# OnOfre_EasyPlug_dev.net
KiCad netlist of a schematic drawn in EAGLE
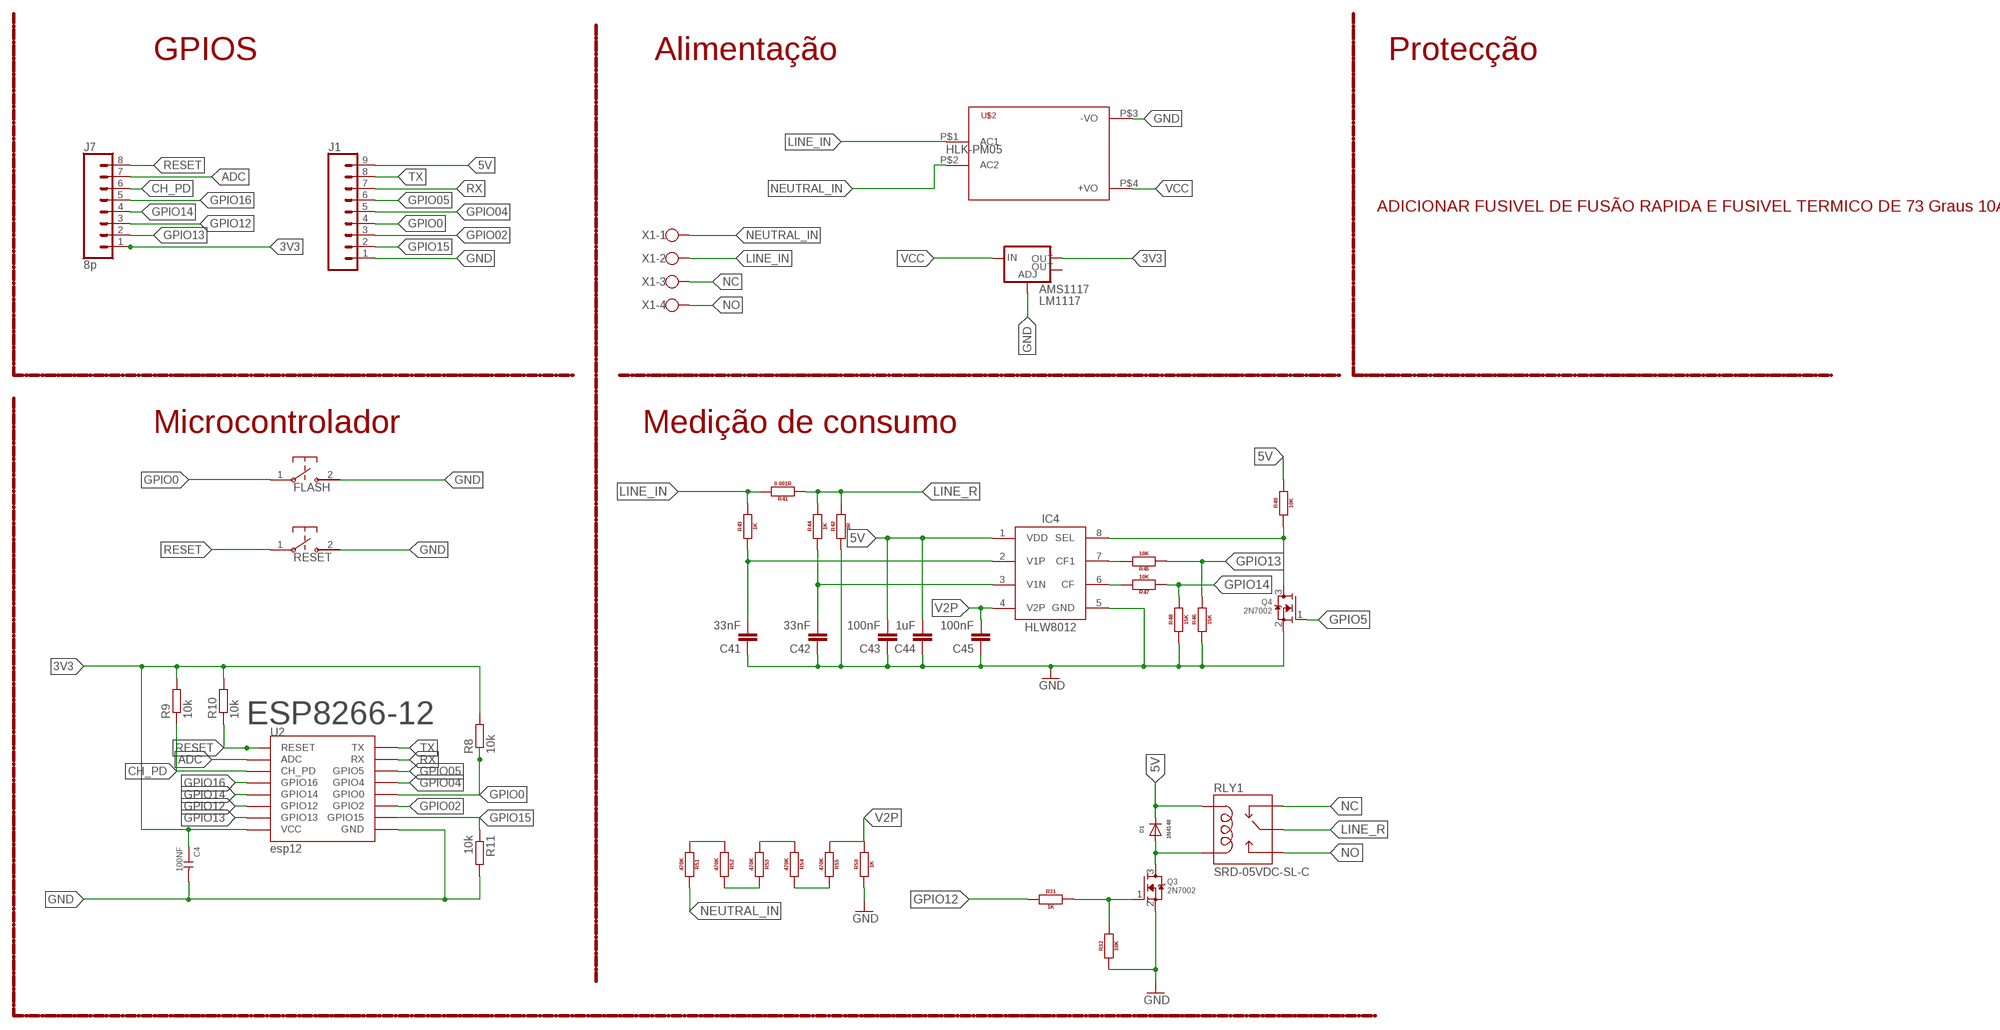
[diagram p0: schematic, sheet 1]

(export (version "E")
  (design (tool "Eeschema 10.0.6"))
  (components
    (comp (ref "AMS1117")
      (value "LM1117")
      (footprint "eagle-import:SOT223")
      (libsource (lib "eagle-import") (part "V_REG_LM1117SOT223"))
    )
    (comp (ref "C4")
      (value "100NF")
      (footprint "eagle-import:C1206")
      (fields (field (name "MPN") "CC1206KKX7RCBB102"))
      (libsource (lib "eagle-import") (part "CERAMIC-1NF-1KV-10%-X7R?(1206)"))
    )
    (comp (ref "C41")
      (value "33nF")
      (footprint "eagle-import:0805")
      (libsource (lib "eagle-import") (part "C-EU0805"))
    )
    (comp (ref "C42")
      (value "33nF")
      (footprint "eagle-import:0805")
      (libsource (lib "eagle-import") (part "C-EU0805"))
    )
    (comp (ref "C43")
      (value "100nF")
      (footprint "eagle-import:0805")
      (libsource (lib "eagle-import") (part "C-EU0805"))
    )
    (comp (ref "C44")
      (value "1uF")
      (footprint "eagle-import:0805")
      (libsource (lib "eagle-import") (part "C-EU0805"))
    )
    (comp (ref "C45")
      (value "100nF")
      (footprint "eagle-import:0805")
      (libsource (lib "eagle-import") (part "C-EU0805"))
    )
    (comp (ref "D1")
      (value "1N4148")
      (footprint "eagle-import:SOD80")
      (libsource (lib "eagle-import") (part "DIODE"))
    )
    (comp (ref "FLASH")
      (value "B3U-1000P-2P-SMD")
      (footprint "eagle-import:B3U-1000P")
      (fields (field (name "MANUFACTURER") "Omron") (field (name "MPN") "B3U-1000P"))
      (libsource (lib "eagle-import") (part "B3U-1000P"))
    )
    (comp (ref "IC4")
      (value "HLW8012")
      (footprint "eagle-import:SOP8")
      (libsource (lib "eagle-import") (part "HLW8012"))
    )
    (comp (ref "J1")
      (value "CONN_09")
      (footprint "eagle-import:1X09")
      (libsource (lib "eagle-import") (part "CONN_09"))
    )
    (comp (ref "J7")
      (value "8p")
      (footprint "eagle-import:1X08")
      (libsource (lib "eagle-import") (part "CONN_08{dblquote}"))
    )
    (comp (ref "Q3")
      (value "2N7002")
      (footprint "eagle-import:SOT23")
      (libsource (lib "eagle-import") (part "MOSFET-NREFLOW"))
    )
    (comp (ref "Q4")
      (value "2N7002")
      (footprint "eagle-import:SOT23")
      (libsource (lib "eagle-import") (part "MOSFET-NREFLOW"))
    )
    (comp (ref "R8")
      (value "10k")
      (footprint "eagle-import:R0603")
      (libsource (lib "eagle-import") (part "R-EU_R0603"))
    )
    (comp (ref "R9")
      (value "10k")
      (footprint "eagle-import:R0603")
      (libsource (lib "eagle-import") (part "R-EU_R0603"))
    )
    (comp (ref "R10")
      (value "10k")
      (footprint "eagle-import:R0603")
      (libsource (lib "eagle-import") (part "R-EU_R0603"))
    )
    (comp (ref "R11")
      (value "10k")
      (footprint "eagle-import:R0603")
      (libsource (lib "eagle-import") (part "R-EU_R0603"))
    )
    (comp (ref "R31")
      (value "1K")
      (footprint "eagle-import:0805")
      (libsource (lib "eagle-import") (part "RESISTOR0805"))
    )
    (comp (ref "R32")
      (value "10K")
      (footprint "eagle-import:0805")
      (libsource (lib "eagle-import") (part "RESISTOR0805"))
    )
    (comp (ref "R41")
      (value "0.001R")
      (footprint "eagle-import:2512")
      (libsource (lib "eagle-import") (part "RESISTOR2512"))
    )
    (comp (ref "R42")
      (value "0R")
      (footprint "eagle-import:1206")
      (libsource (lib "eagle-import") (part "RESISTOR1206"))
    )
    (comp (ref "R43")
      (value "1K")
      (footprint "eagle-import:0805")
      (libsource (lib "eagle-import") (part "RESISTOR0805"))
    )
    (comp (ref "R44")
      (value "1K")
      (footprint "eagle-import:0805")
      (libsource (lib "eagle-import") (part "RESISTOR0805"))
    )
    (comp (ref "R45")
      (value "10K")
      (footprint "eagle-import:0805")
      (libsource (lib "eagle-import") (part "RESISTOR0805"))
    )
    (comp (ref "R46")
      (value "15K")
      (footprint "eagle-import:0805")
      (libsource (lib "eagle-import") (part "RESISTOR0805"))
    )
    (comp (ref "R47")
      (value "10K")
      (footprint "eagle-import:0805")
      (libsource (lib "eagle-import") (part "RESISTOR0805"))
    )
    (comp (ref "R48")
      (value "15K")
      (footprint "eagle-import:0805")
      (libsource (lib "eagle-import") (part "RESISTOR0805"))
    )
    (comp (ref "R49")
      (value "10K")
      (footprint "eagle-import:0805")
      (libsource (lib "eagle-import") (part "RESISTOR0805"))
    )
    (comp (ref "R50")
      (value "1K")
      (footprint "eagle-import:0805")
      (libsource (lib "eagle-import") (part "RESISTOR0805"))
    )
    (comp (ref "R51")
      (value "470K")
      (footprint "eagle-import:0805")
      (libsource (lib "eagle-import") (part "RESISTOR0805"))
    )
    (comp (ref "R52")
      (value "470K")
      (footprint "eagle-import:0805")
      (libsource (lib "eagle-import") (part "RESISTOR0805"))
    )
    (comp (ref "R53")
      (value "470K")
      (footprint "eagle-import:0805")
      (libsource (lib "eagle-import") (part "RESISTOR0805"))
    )
    (comp (ref "R54")
      (value "470K")
      (footprint "eagle-import:0805")
      (libsource (lib "eagle-import") (part "RESISTOR0805"))
    )
    (comp (ref "R55")
      (value "470K")
      (footprint "eagle-import:0805")
      (libsource (lib "eagle-import") (part "RESISTOR0805"))
    )
    (comp (ref "RESET")
      (value "B3U-1000P-2P-SMD")
      (footprint "eagle-import:B3U-1000P")
      (fields (field (name "MANUFACTURER") "Omron") (field (name "MPN") "B3U-1000P"))
      (libsource (lib "eagle-import") (part "B3U-1000P"))
    )
    (comp (ref "RLY1")
      (value "SRD-05VDC-SL-C")
      (footprint "eagle-import:SRD-5VDC-SL-C")
      (libsource (lib "eagle-import") (part "RELAYSONGLE"))
    )
    (comp (ref "U$2")
      (value "HKLPM01")
      (footprint "eagle-import:HKLPM01")
      (libsource (lib "eagle-import") (part "HKLPM01"))
    )
    (comp (ref "U2")
      (value "esp12")
      (footprint "eagle-import:ESP12-SMD")
      (libsource (lib "eagle-import") (part "ESP12SMD"))
    )
    (comp (ref "X1")
      (value "W237-4")
      (footprint "eagle-import:W237-4")
      (libsource (lib "eagle-import") (part "W237-4"))
    )
  )
  (nets
    (net (code "1") (name "3V3") (class "Default")
      (node (ref "AMS1117") (pin "2") (pinfunction "OUT_2") (pintype "output"))
      (node (ref "C4") (pin "1") (pinfunction "1_1") (pintype "passive"))
      (node (ref "J7") (pin "1") (pinfunction "1_1") (pintype "passive"))
      (node (ref "R10") (pin "2") (pinfunction "2_2") (pintype "passive"))
      (node (ref "R8") (pin "2") (pinfunction "2_2") (pintype "passive"))
      (node (ref "R9") (pin "2") (pinfunction "2_2") (pintype "passive"))
      (node (ref "U2") (pin "VCC") (pinfunction "VCC_VCC") (pintype "bidirectional"))
    )
    (net (code "2") (name "5V") (class "Default")
      (node (ref "C43") (pin "2") (pinfunction "2_2") (pintype "passive"))
      (node (ref "C44") (pin "2") (pinfunction "2_2") (pintype "passive"))
      (node (ref "D1") (pin "2") (pinfunction "C_2") (pintype "passive"))
      (node (ref "IC4") (pin "1") (pinfunction "VDD_1") (pintype "power_in"))
      (node (ref "J1") (pin "9") (pinfunction "9_9") (pintype "passive"))
      (node (ref "R49") (pin "2") (pinfunction "2_2") (pintype "passive"))
      (node (ref "RLY1") (pin "COIL1") (pinfunction "COIL1_COIL1") (pintype "bidirectional"))
    )
    (net (code "3") (name "ADC") (class "Default")
      (node (ref "J7") (pin "7") (pinfunction "7_7") (pintype "passive"))
      (node (ref "U2") (pin "ADC") (pinfunction "ADC_ADC") (pintype "bidirectional"))
    )
    (net (code "4") (name "CH_PD") (class "Default")
      (node (ref "J7") (pin "6") (pinfunction "6_6") (pintype "passive"))
      (node (ref "R9") (pin "1") (pinfunction "1_1") (pintype "passive"))
      (node (ref "U2") (pin "CH_PD") (pinfunction "CH_PD_CH_PD") (pintype "bidirectional"))
    )
    (net (code "5") (name "GND") (class "Default")
      (node (ref "AMS1117") (pin "1") (pinfunction "ADJ_1") (pintype "input"))
      (node (ref "C4") (pin "2") (pinfunction "2_2") (pintype "passive"))
      (node (ref "C41") (pin "1") (pinfunction "1_1") (pintype "passive"))
      (node (ref "C42") (pin "1") (pinfunction "1_1") (pintype "passive"))
      (node (ref "C43") (pin "1") (pinfunction "1_1") (pintype "passive"))
      (node (ref "C44") (pin "1") (pinfunction "1_1") (pintype "passive"))
      (node (ref "C45") (pin "1") (pinfunction "1_1") (pintype "passive"))
      (node (ref "FLASH") (pin "2") (pinfunction "P$2_2") (pintype "passive"))
      (node (ref "IC4") (pin "5") (pinfunction "GND_5") (pintype "power_in"))
      (node (ref "J1") (pin "1") (pinfunction "1_1") (pintype "passive"))
      (node (ref "Q3") (pin "2") (pinfunction "S_2") (pintype "bidirectional"))
      (node (ref "Q4") (pin "2") (pinfunction "S_2") (pintype "bidirectional"))
      (node (ref "R11") (pin "2") (pinfunction "2_2") (pintype "passive"))
      (node (ref "R32") (pin "1") (pinfunction "1_1") (pintype "passive"))
      (node (ref "R42") (pin "1") (pinfunction "1_1") (pintype "passive"))
      (node (ref "R46") (pin "1") (pinfunction "1_1") (pintype "passive"))
      (node (ref "R48") (pin "1") (pinfunction "1_1") (pintype "passive"))
      (node (ref "R50") (pin "1") (pinfunction "1_1") (pintype "passive"))
      (node (ref "RESET") (pin "2") (pinfunction "P$2_2") (pintype "passive"))
      (node (ref "U$2") (pin "P$3") (pinfunction "-VO_P$3") (pintype "bidirectional"))
      (node (ref "U2") (pin "GND") (pinfunction "GND_GND") (pintype "bidirectional"))
    )
    (net (code "6") (name "GPIO0") (class "Default")
      (node (ref "FLASH") (pin "1") (pinfunction "P$1_1") (pintype "passive"))
      (node (ref "J1") (pin "4") (pinfunction "4_4") (pintype "passive"))
      (node (ref "R8") (pin "1") (pinfunction "1_1") (pintype "passive"))
      (node (ref "U2") (pin "GPIO0") (pinfunction "GPIO0_GPIO0") (pintype "bidirectional"))
    )
    (net (code "7") (name "GPIO02") (class "Default")
      (node (ref "J1") (pin "3") (pinfunction "3_3") (pintype "passive"))
      (node (ref "U2") (pin "GPIO2") (pinfunction "GPIO2_GPIO2") (pintype "bidirectional"))
    )
    (net (code "8") (name "GPIO04") (class "Default")
      (node (ref "J1") (pin "5") (pinfunction "5_5") (pintype "passive"))
      (node (ref "U2") (pin "GPIO4") (pinfunction "GPIO4_GPIO4") (pintype "bidirectional"))
    )
    (net (code "9") (name "GPIO5") (class "Default")
      (node (ref "Q4") (pin "1") (pinfunction "G_1") (pintype "bidirectional"))
    )
    (net (code "10") (name "GPIO05") (class "Default")
      (node (ref "J1") (pin "6") (pinfunction "6_6") (pintype "passive"))
      (node (ref "U2") (pin "GPIO5") (pinfunction "GPIO5_GPIO5") (pintype "bidirectional"))
    )
    (net (code "11") (name "GPIO12") (class "Default")
      (node (ref "J7") (pin "3") (pinfunction "3_3") (pintype "passive"))
      (node (ref "R31") (pin "1") (pinfunction "1_1") (pintype "passive"))
      (node (ref "U2") (pin "GPIO12") (pinfunction "GPIO12_GPIO12") (pintype "bidirectional"))
    )
    (net (code "12") (name "GPIO13") (class "Default")
      (node (ref "J7") (pin "2") (pinfunction "2_2") (pintype "passive"))
      (node (ref "R45") (pin "1") (pinfunction "1_1") (pintype "passive"))
      (node (ref "R46") (pin "2") (pinfunction "2_2") (pintype "passive"))
      (node (ref "U2") (pin "GPIO13") (pinfunction "GPIO13_GPIO13") (pintype "bidirectional"))
    )
    (net (code "13") (name "GPIO14") (class "Default")
      (node (ref "J7") (pin "4") (pinfunction "4_4") (pintype "passive"))
      (node (ref "R47") (pin "1") (pinfunction "1_1") (pintype "passive"))
      (node (ref "R48") (pin "2") (pinfunction "2_2") (pintype "passive"))
      (node (ref "U2") (pin "GPIO14") (pinfunction "GPIO14_GPIO14") (pintype "bidirectional"))
    )
    (net (code "14") (name "GPIO15") (class "Default")
      (node (ref "J1") (pin "2") (pinfunction "2_2") (pintype "passive"))
      (node (ref "R11") (pin "1") (pinfunction "1_1") (pintype "passive"))
      (node (ref "U2") (pin "GPIO15") (pinfunction "GPIO15_GPIO15") (pintype "bidirectional"))
    )
    (net (code "15") (name "GPIO16") (class "Default")
      (node (ref "J7") (pin "5") (pinfunction "5_5") (pintype "passive"))
      (node (ref "U2") (pin "GPIO16") (pinfunction "GPIO16_GPIO16") (pintype "bidirectional"))
    )
    (net (code "16") (name "LINE_IN") (class "Default")
      (node (ref "R41") (pin "2") (pinfunction "2_2") (pintype "passive"))
      (node (ref "R43") (pin "2") (pinfunction "2_2") (pintype "passive"))
      (node (ref "U$2") (pin "P$1") (pinfunction "AC1_P$1") (pintype "bidirectional"))
      (node (ref "X1") (pin "2") (pinfunction "KL_2") (pintype "passive"))
    )
    (net (code "17") (name "LINE_R") (class "Default")
      (node (ref "R41") (pin "1") (pinfunction "1_1") (pintype "passive"))
      (node (ref "R42") (pin "2") (pinfunction "2_2") (pintype "passive"))
      (node (ref "R44") (pin "2") (pinfunction "2_2") (pintype "passive"))
      (node (ref "RLY1") (pin "COMMON") (pinfunction "MAIN_COMMON") (pintype "bidirectional"))
    )
    (net (code "18") (name "NC") (class "Default")
      (node (ref "RLY1") (pin "CLOSED") (pinfunction "NC_CLOSED") (pintype "bidirectional"))
      (node (ref "X1") (pin "3") (pinfunction "KL_3") (pintype "passive"))
    )
    (net (code "19") (name "NEUTRAL_IN") (class "Default")
      (node (ref "R51") (pin "2") (pinfunction "2_2") (pintype "passive"))
      (node (ref "U$2") (pin "P$2") (pinfunction "AC2_P$2") (pintype "bidirectional"))
      (node (ref "X1") (pin "1") (pinfunction "KL_1") (pintype "passive"))
    )
    (net (code "20") (name "NO") (class "Default")
      (node (ref "RLY1") (pin "OPEN") (pinfunction "NO_OPEN") (pintype "bidirectional"))
      (node (ref "X1") (pin "4") (pinfunction "KL_4") (pintype "passive"))
    )
    (net (code "21") (name "Net-(D1-A)") (class "Default")
      (node (ref "D1") (pin "1") (pinfunction "A_1") (pintype "passive"))
      (node (ref "Q3") (pin "3") (pinfunction "D_3") (pintype "bidirectional"))
      (node (ref "RLY1") (pin "COIL2") (pinfunction "COIL2_COIL2") (pintype "bidirectional"))
    )
    (net (code "22") (name "Net-(IC4-CF)") (class "Default")
      (node (ref "IC4") (pin "6") (pinfunction "CF_6") (pintype "output"))
      (node (ref "R47") (pin "2") (pinfunction "2_2") (pintype "passive"))
    )
    (net (code "23") (name "Net-(IC4-CF1)") (class "Default")
      (node (ref "IC4") (pin "7") (pinfunction "CF1_7") (pintype "output"))
      (node (ref "R45") (pin "2") (pinfunction "2_2") (pintype "passive"))
    )
    (net (code "24") (name "Net-(IC4-SEL)") (class "Default")
      (node (ref "IC4") (pin "8") (pinfunction "SEL_8") (pintype "input"))
      (node (ref "Q4") (pin "3") (pinfunction "D_3") (pintype "bidirectional"))
      (node (ref "R49") (pin "1") (pinfunction "1_1") (pintype "passive"))
    )
    (net (code "25") (name "Net-(IC4-V1N)") (class "Default")
      (node (ref "C42") (pin "2") (pinfunction "2_2") (pintype "passive"))
      (node (ref "IC4") (pin "3") (pinfunction "V1N_3") (pintype "input"))
      (node (ref "R44") (pin "1") (pinfunction "1_1") (pintype "passive"))
    )
    (net (code "26") (name "Net-(IC4-V1P)") (class "Default")
      (node (ref "C41") (pin "2") (pinfunction "2_2") (pintype "passive"))
      (node (ref "IC4") (pin "2") (pinfunction "V1P_2") (pintype "input"))
      (node (ref "R43") (pin "1") (pinfunction "1_1") (pintype "passive"))
    )
    (net (code "27") (name "Net-(Q3-G)") (class "Default")
      (node (ref "Q3") (pin "1") (pinfunction "G_1") (pintype "bidirectional"))
      (node (ref "R31") (pin "2") (pinfunction "2_2") (pintype "passive"))
      (node (ref "R32") (pin "2") (pinfunction "2_2") (pintype "passive"))
    )
    (net (code "28") (name "Net-(R51-Pad1)") (class "Default")
      (node (ref "R51") (pin "1") (pinfunction "1_1") (pintype "passive"))
      (node (ref "R52") (pin "1") (pinfunction "1_1") (pintype "passive"))
    )
    (net (code "29") (name "Net-(R52-Pad2)") (class "Default")
      (node (ref "R52") (pin "2") (pinfunction "2_2") (pintype "passive"))
      (node (ref "R53") (pin "2") (pinfunction "2_2") (pintype "passive"))
    )
    (net (code "30") (name "Net-(R53-Pad1)") (class "Default")
      (node (ref "R53") (pin "1") (pinfunction "1_1") (pintype "passive"))
      (node (ref "R54") (pin "1") (pinfunction "1_1") (pintype "passive"))
    )
    (net (code "31") (name "Net-(R54-Pad2)") (class "Default")
      (node (ref "R54") (pin "2") (pinfunction "2_2") (pintype "passive"))
      (node (ref "R55") (pin "2") (pinfunction "2_2") (pintype "passive"))
    )
    (net (code "32") (name "RESET") (class "Default")
      (node (ref "J7") (pin "8") (pinfunction "8_8") (pintype "passive"))
      (node (ref "R10") (pin "1") (pinfunction "1_1") (pintype "passive"))
      (node (ref "RESET") (pin "1") (pinfunction "P$1_1") (pintype "passive"))
      (node (ref "U2") (pin "RESET") (pinfunction "RESET_RESET") (pintype "bidirectional"))
    )
    (net (code "33") (name "RX") (class "Default")
      (node (ref "J1") (pin "7") (pinfunction "7_7") (pintype "passive"))
      (node (ref "U2") (pin "RXD0") (pinfunction "RX_RXD0") (pintype "bidirectional"))
    )
    (net (code "34") (name "TX") (class "Default")
      (node (ref "J1") (pin "8") (pinfunction "8_8") (pintype "passive"))
      (node (ref "U2") (pin "TXD0") (pinfunction "TX_TXD0") (pintype "bidirectional"))
    )
    (net (code "35") (name "V2P") (class "Default")
      (node (ref "C45") (pin "2") (pinfunction "2_2") (pintype "passive"))
      (node (ref "IC4") (pin "4") (pinfunction "V2P_4") (pintype "input"))
      (node (ref "R50") (pin "2") (pinfunction "2_2") (pintype "passive"))
      (node (ref "R55") (pin "1") (pinfunction "1_1") (pintype "passive"))
    )
    (net (code "36") (name "VCC") (class "Default")
      (node (ref "AMS1117") (pin "3") (pinfunction "IN_3") (pintype "input"))
      (node (ref "U$2") (pin "P$4") (pinfunction "+VO_P$4") (pintype "bidirectional"))
    )
    (net (code "37") (name "unconnected-(AMS1117-OUT-Pad4)") (class "Default")
      (node (ref "AMS1117") (pin "4") (pinfunction "OUT_4") (pintype "output"))
    )
  )
)
